# LickDetector_8mm.net
KiCad netlist of a schematic drawn in EAGLE
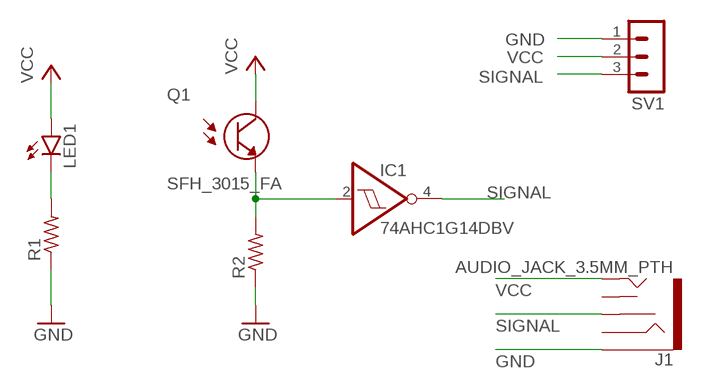
[diagram p0: schematic, sheet 1]

(export (version "E")
  (design (tool "Eeschema 10.0.6"))
  (components
    (comp (ref "IC1")
      (value "74AHC1G14DBV")
      (footprint "eagle-import:SOT23-5")
      (libsource (lib "eagle-import") (part "741G14DBVAHC"))
    )
    (comp (ref "J1")
      (value "AUDIO_JACK_3.5MM_PTH")
      (footprint "eagle-import:AUDIO-JACK")
      (libsource (lib "eagle-import") (part "AUDIO_JACK_3.5MM_PTH"))
    )
    (comp (ref "LED1")
      (value "LEDCHIPLED_1206")
      (footprint "eagle-import:CHIPLED_1206")
      (libsource (lib "eagle-import") (part "LEDCHIPLED_1206"))
    )
    (comp (ref "Q1")
      (value "SFH_3015_FA")
      (footprint "eagle-import:XDCR_SFH_3015_FA")
      (fields
        (field (name "DIGI-KEY_PART_NUMBER") "475-2914-1-ND")
        (field (name "MF") "OSRAM Opto")
        (field (name "MP") "SFH 3015 FA")
      )
      (libsource (lib "eagle-import") (part "SFH_3015_FA"))
    )
    (comp (ref "R1")
      (value "R-US_M1206")
      (footprint "eagle-import:M1206")
      (libsource (lib "eagle-import") (part "R-US_M1206"))
    )
    (comp (ref "R2")
      (value "R-US_M1206")
      (footprint "eagle-import:M1206")
      (libsource (lib "eagle-import") (part "R-US_M1206"))
    )
    (comp (ref "SV1")
      (value "MA03-1")
      (footprint "eagle-import:MA03-1")
      (libsource (lib "eagle-import") (part "MA03-1"))
    )
  )
  (nets
    (net (code "1") (name "/SIGNAL") (class "Default")
      (node (ref "IC1") (pin "4") (pinfunction "O_4") (pintype "output"))
      (node (ref "J1") (pin "RSH") (pinfunction "RSH_RSH") (pintype "bidirectional"))
      (node (ref "SV1") (pin "3") (pinfunction "3_3") (pintype "passive"))
    )
    (net (code "2") (name "GND") (class "Default")
      (node (ref "J1") (pin "SLEEVE") (pinfunction "SLEEVE_SLEEVE") (pintype "bidirectional"))
      (node (ref "R1") (pin "1") (pinfunction "1_1") (pintype "passive"))
      (node (ref "R2") (pin "1") (pinfunction "1_1") (pintype "passive"))
      (node (ref "SV1") (pin "1") (pinfunction "1_1") (pintype "passive"))
    )
    (net (code "3") (name "Net-(IC1A-I)") (class "Default")
      (node (ref "IC1") (pin "2") (pinfunction "I_2") (pintype "input"))
      (node (ref "Q1") (pin "1") (pinfunction "E_1") (pintype "passive"))
      (node (ref "R2") (pin "2") (pinfunction "2_2") (pintype "passive"))
    )
    (net (code "4") (name "Net-(LED1-PadC)") (class "Default")
      (node (ref "LED1") (pin "C") (pinfunction "C_C") (pintype "passive"))
      (node (ref "R1") (pin "2") (pinfunction "2_2") (pintype "passive"))
    )
    (net (code "5") (name "VCC") (class "Default")
      (node (ref "J1") (pin "TIP") (pinfunction "TIP_TIP") (pintype "bidirectional"))
      (node (ref "LED1") (pin "A") (pinfunction "A_A") (pintype "passive"))
      (node (ref "Q1") (pin "2") (pinfunction "C_2") (pintype "passive"))
      (node (ref "SV1") (pin "2") (pinfunction "2_2") (pintype "passive"))
    )
    (net (code "6") (name "unconnected-(J1-PadRING)") (class "Default")
      (node (ref "J1") (pin "RING") (pinfunction "RING_RING") (pintype "bidirectional"))
    )
    (net (code "7") (name "unconnected-(J1-PadTSH)") (class "Default")
      (node (ref "J1") (pin "TSH") (pinfunction "TSH_TSH") (pintype "bidirectional"))
    )
  )
)
